# MinipHV3_2.net
KiCad netlist of a schematic drawn in EAGLE
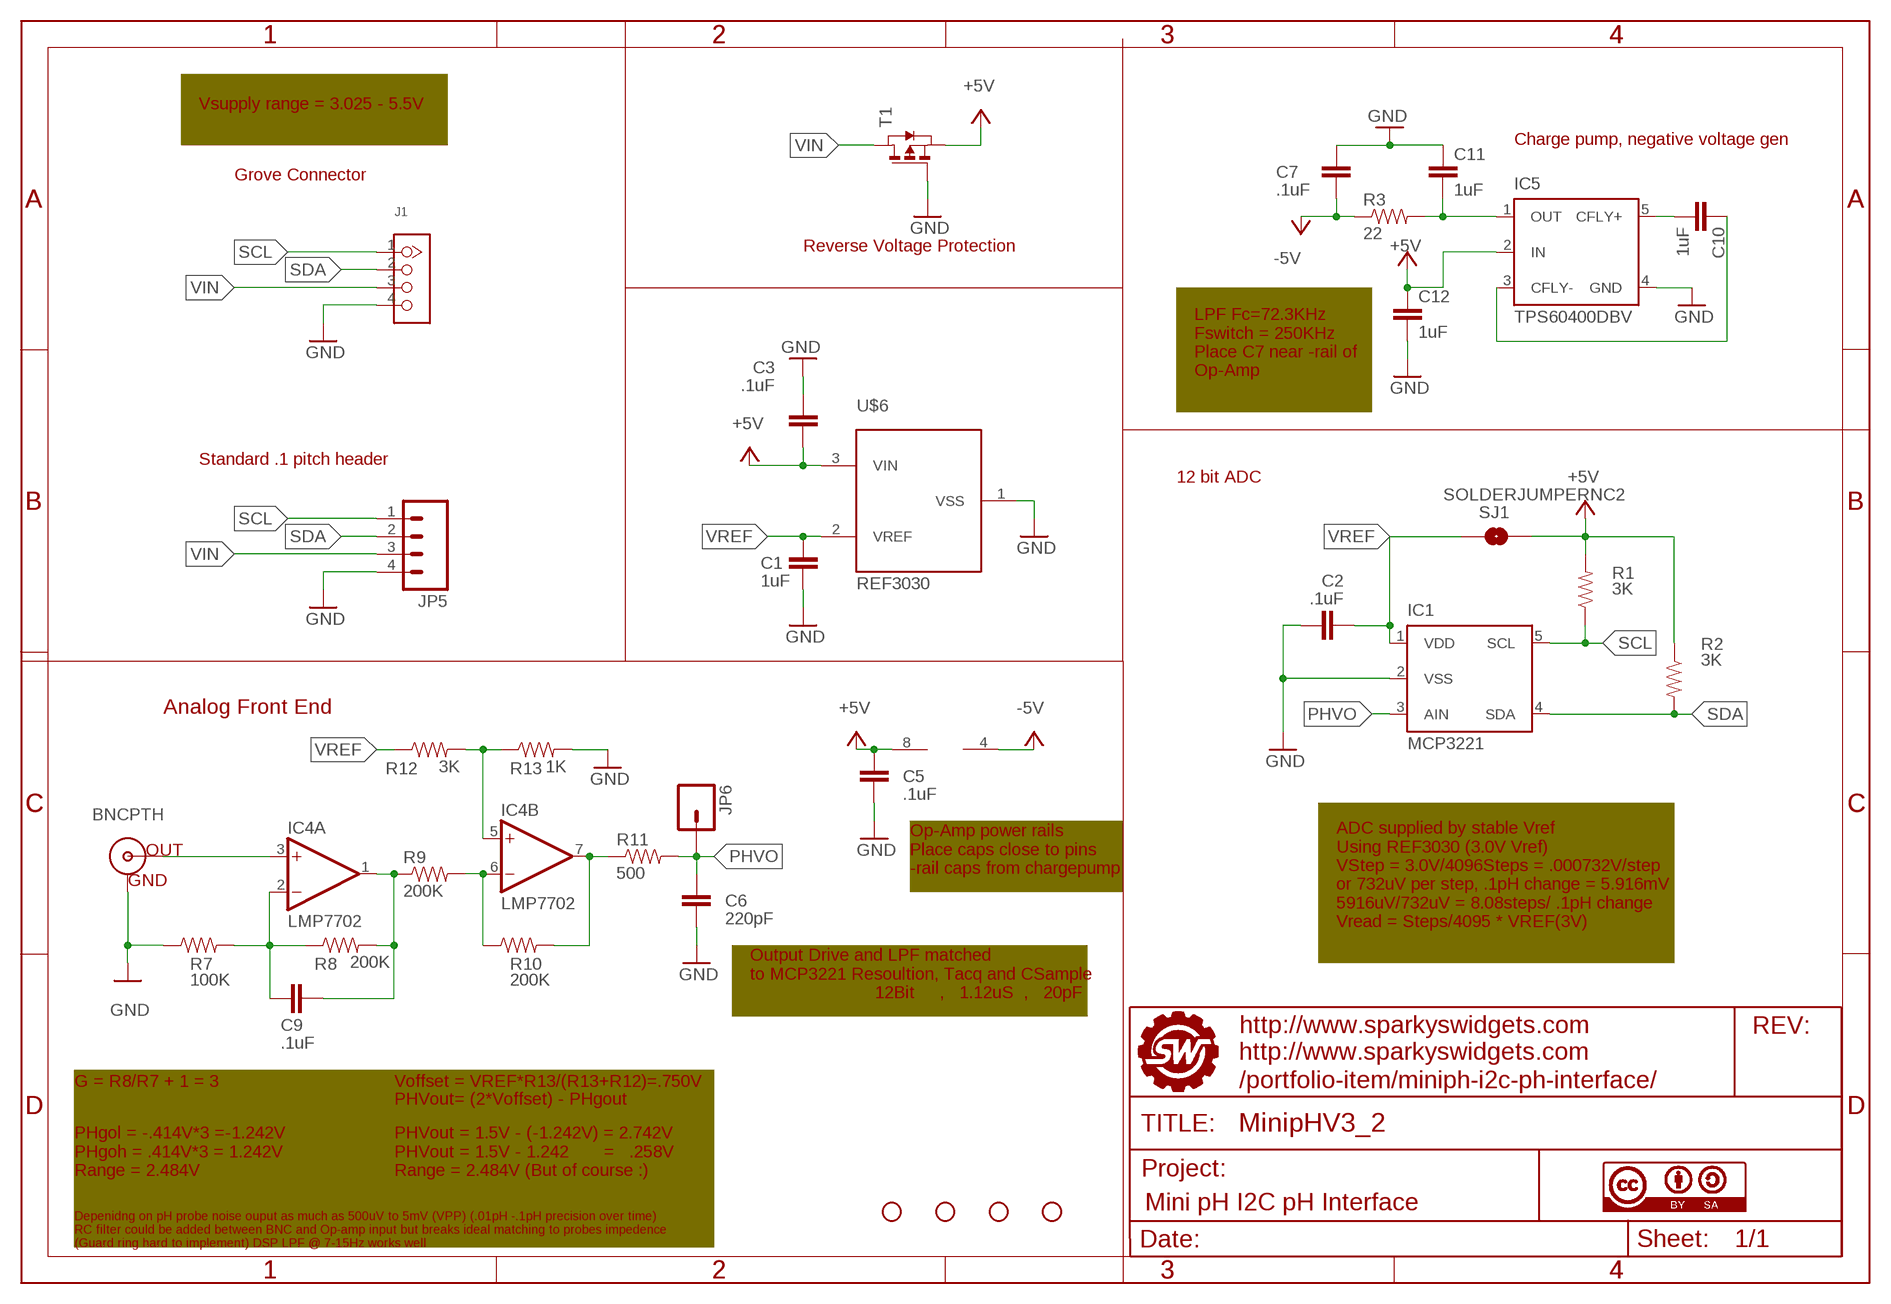
[diagram p0: schematic, sheet 1]

(export (version "E")
  (design (tool "Eeschema 10.0.6"))
  (components
    (comp (ref "C1")
      (value "1uF")
      (footprint "eagle-import:0805")
      (libsource (lib "eagle-import") (part "CAP0805"))
    )
    (comp (ref "C2")
      (value ".1uF")
      (footprint "eagle-import:0805")
      (libsource (lib "eagle-import") (part "CAP0805"))
    )
    (comp (ref "C3")
      (value ".1uF")
      (footprint "eagle-import:0805")
      (libsource (lib "eagle-import") (part "CAP0805"))
    )
    (comp (ref "C5")
      (value ".1uF")
      (footprint "eagle-import:0805")
      (libsource (lib "eagle-import") (part "CAP0805"))
    )
    (comp (ref "C6")
      (value "220pF")
      (footprint "eagle-import:0805")
      (libsource (lib "eagle-import") (part "CAP0805"))
    )
    (comp (ref "C7")
      (value ".1uF")
      (footprint "eagle-import:0805")
      (libsource (lib "eagle-import") (part "CAP0805"))
    )
    (comp (ref "C9")
      (value ".1uF")
      (footprint "eagle-import:0805")
      (libsource (lib "eagle-import") (part "CAP0805"))
    )
    (comp (ref "C10")
      (value "1uF")
      (footprint "eagle-import:0805")
      (libsource (lib "eagle-import") (part "CAP0805"))
    )
    (comp (ref "C11")
      (value "1uF")
      (footprint "eagle-import:0805")
      (libsource (lib "eagle-import") (part "CAP0805"))
    )
    (comp (ref "C12")
      (value "1uF")
      (footprint "eagle-import:0805")
      (libsource (lib "eagle-import") (part "CAP0805"))
    )
    (comp (ref "IC1")
      (value "MCP3221")
      (footprint "eagle-import:SOT23-DBV")
      (libsource (lib "eagle-import") (part "MCP3221"))
    )
    (comp (ref "IC4")
      (value "LMP7702")
      (footprint "eagle-import:SO08")
      (libsource (lib "eagle-import") (part "LM358D"))
    )
    (comp (ref "IC5")
      (value "TPS60400DBV")
      (footprint "eagle-import:SOT23-DBV")
      (libsource (lib "eagle-import") (part "TPS60400DBV"))
    )
    (comp (ref "J1")
      (value "TWIG-4P-2.0-2.0")
      (footprint "eagle-import:4P-2.0")
      (libsource (lib "eagle-import") (part "TWIG-4P-2.0-2.0"))
    )
    (comp (ref "JP1")
      (value "STAND-OFF")
      (footprint "eagle-import:STAND-OFF")
      (libsource (lib "eagle-import") (part "STAND-OFF"))
    )
    (comp (ref "JP2")
      (value "STAND-OFF")
      (footprint "eagle-import:STAND-OFF")
      (libsource (lib "eagle-import") (part "STAND-OFF"))
    )
    (comp (ref "JP3")
      (value "STAND-OFF")
      (footprint "eagle-import:STAND-OFF")
      (libsource (lib "eagle-import") (part "STAND-OFF"))
    )
    (comp (ref "JP4")
      (value "STAND-OFF")
      (footprint "eagle-import:STAND-OFF")
      (libsource (lib "eagle-import") (part "STAND-OFF"))
    )
    (comp (ref "JP5")
      (value "M04PTH")
      (footprint "eagle-import:1X04")
      (libsource (lib "eagle-import") (part "M04PTH"))
    )
    (comp (ref "JP6")
      (value "M01PTH")
      (footprint "eagle-import:1X01")
      (libsource (lib "eagle-import") (part "M01PTH"))
    )
    (comp (ref "R1")
      (value "3K")
      (footprint "eagle-import:0805")
      (libsource (lib "eagle-import") (part "RESISTOR0805-RES"))
    )
    (comp (ref "R2")
      (value "3K")
      (footprint "eagle-import:0805")
      (libsource (lib "eagle-import") (part "RESISTOR0805-RES"))
    )
    (comp (ref "R3")
      (value "22")
      (footprint "eagle-import:0805")
      (libsource (lib "eagle-import") (part "RESISTOR0805-RES"))
    )
    (comp (ref "R7")
      (value "100K")
      (footprint "eagle-import:0805")
      (libsource (lib "eagle-import") (part "RESISTOR0805-RES"))
    )
    (comp (ref "R8")
      (value "200K")
      (footprint "eagle-import:0805")
      (libsource (lib "eagle-import") (part "RESISTOR0805-RES"))
    )
    (comp (ref "R9")
      (value "200K")
      (footprint "eagle-import:0805")
      (libsource (lib "eagle-import") (part "RESISTOR0805-RES"))
    )
    (comp (ref "R10")
      (value "200K")
      (footprint "eagle-import:0805")
      (libsource (lib "eagle-import") (part "RESISTOR0805-RES"))
    )
    (comp (ref "R11")
      (value "500")
      (footprint "eagle-import:0805")
      (libsource (lib "eagle-import") (part "RESISTOR0805-RES"))
    )
    (comp (ref "R12")
      (value "3K")
      (footprint "eagle-import:0805")
      (libsource (lib "eagle-import") (part "RESISTOR0805-RES"))
    )
    (comp (ref "R13")
      (value "1K")
      (footprint "eagle-import:0805")
      (libsource (lib "eagle-import") (part "RESISTOR0805-RES"))
    )
    (comp (ref "SJ1")
      (value "SOLDERJUMPERNC2")
      (footprint "eagle-import:SJ_2S-NOTRACE")
      (libsource (lib "eagle-import") (part "SOLDERJUMPERNC2"))
    )
    (comp (ref "T1")
      (value "PMOSSOT23")
      (footprint "eagle-import:SOT-23")
      (libsource (lib "eagle-import") (part "PMOSSOT23"))
    )
    (comp (ref "U$2")
      (value "BNCPTH")
      (footprint "eagle-import:BNC")
      (libsource (lib "eagle-import") (part "BNCPTH"))
    )
    (comp (ref "U$4")
      (value "FRAME_MINIPH")
      (footprint "eagle-import:SWPCBLOGOWITHINFO")
      (fields
        (field (name "PROJECT") "Mini pH I2C pH Interface")
        (field (name "URL1") "/portfolio-item/miniph-i2c-ph-interface/")
      )
      (libsource (lib "eagle-import") (part "FRAME_MINIPH"))
    )
    (comp (ref "U$5")
      (value "CC-BY-SA")
      (footprint "eagle-import:CC-BY-SA")
      (libsource (lib "eagle-import") (part "CC-BY-SA"))
    )
    (comp (ref "U$6")
      (value "REF3030")
      (footprint "eagle-import:SOT-23")
      (libsource (lib "eagle-import") (part "MCP1541"))
    )
  )
  (nets
    (net (code "1") (name "+5V") (class "Default")
      (node (ref "C12") (pin "1") (pinfunction "1_1") (pintype "passive"))
      (node (ref "C3") (pin "1") (pinfunction "1_1") (pintype "passive"))
      (node (ref "C5") (pin "1") (pinfunction "1_1") (pintype "passive"))
      (node (ref "IC4") (pin "8") (pinfunction "V+_8") (pintype "power_in"))
      (node (ref "IC5") (pin "2") (pinfunction "IN_2") (pintype "input"))
      (node (ref "R1") (pin "2") (pinfunction "2_2") (pintype "passive"))
      (node (ref "R2") (pin "1") (pinfunction "1_1") (pintype "passive"))
      (node (ref "SJ1") (pin "2") (pinfunction "2_2") (pintype "passive"))
      (node (ref "T1") (pin "2") (pinfunction "S_2") (pintype "passive"))
      (node (ref "U$6") (pin "3") (pinfunction "VIN_3") (pintype "power_in"))
    )
    (net (code "2") (name "-5V") (class "Default")
      (node (ref "C7") (pin "2") (pinfunction "2_2") (pintype "passive"))
      (node (ref "IC4") (pin "4") (pinfunction "V-_4") (pintype "power_in"))
      (node (ref "R3") (pin "1") (pinfunction "1_1") (pintype "passive"))
    )
    (net (code "3") (name "GND") (class "Default")
      (node (ref "C1") (pin "2") (pinfunction "2_2") (pintype "passive"))
      (node (ref "C11") (pin "1") (pinfunction "1_1") (pintype "passive"))
      (node (ref "C12") (pin "2") (pinfunction "2_2") (pintype "passive"))
      (node (ref "C2") (pin "1") (pinfunction "1_1") (pintype "passive"))
      (node (ref "C3") (pin "2") (pinfunction "2_2") (pintype "passive"))
      (node (ref "C5") (pin "2") (pinfunction "2_2") (pintype "passive"))
      (node (ref "C6") (pin "2") (pinfunction "2_2") (pintype "passive"))
      (node (ref "C7") (pin "1") (pinfunction "1_1") (pintype "passive"))
      (node (ref "IC1") (pin "2") (pinfunction "VSS_2") (pintype "power_in"))
      (node (ref "IC5") (pin "4") (pinfunction "GND_4") (pintype "passive"))
      (node (ref "J1") (pin "4") (pinfunction "4_4") (pintype "bidirectional"))
      (node (ref "JP5") (pin "4") (pinfunction "4_4") (pintype "passive"))
      (node (ref "R13") (pin "2") (pinfunction "2_2") (pintype "passive"))
      (node (ref "R7") (pin "1") (pinfunction "1_1") (pintype "passive"))
      (node (ref "T1") (pin "3") (pinfunction "G_3") (pintype "passive"))
      (node (ref "U$2") (pin "GND") (pinfunction "GND_GND") (pintype "bidirectional"))
      (node (ref "U$6") (pin "1") (pinfunction "VSS_1") (pintype "power_in"))
    )
    (net (code "4") (name "Net-(IC4A-+IN)") (class "Default")
      (node (ref "IC4") (pin "3") (pinfunction "+IN_3") (pintype "input"))
      (node (ref "U$2") (pin "S") (pinfunction "OUT_S") (pintype "bidirectional"))
    )
    (net (code "5") (name "Net-(IC4A--IN)") (class "Default")
      (node (ref "C9") (pin "2") (pinfunction "2_2") (pintype "passive"))
      (node (ref "IC4") (pin "2") (pinfunction "-IN_2") (pintype "input"))
      (node (ref "R7") (pin "2") (pinfunction "2_2") (pintype "passive"))
      (node (ref "R8") (pin "1") (pinfunction "1_1") (pintype "passive"))
    )
    (net (code "6") (name "Net-(IC4A-OUT)") (class "Default")
      (node (ref "C9") (pin "1") (pinfunction "1_1") (pintype "passive"))
      (node (ref "IC4") (pin "1") (pinfunction "OUT_1") (pintype "output"))
      (node (ref "R8") (pin "2") (pinfunction "2_2") (pintype "passive"))
      (node (ref "R9") (pin "1") (pinfunction "1_1") (pintype "passive"))
    )
    (net (code "7") (name "Net-(IC4B-+IN)") (class "Default")
      (node (ref "IC4") (pin "5") (pinfunction "+IN_5") (pintype "input"))
      (node (ref "R12") (pin "2") (pinfunction "2_2") (pintype "passive"))
      (node (ref "R13") (pin "1") (pinfunction "1_1") (pintype "passive"))
    )
    (net (code "8") (name "Net-(IC4B--IN)") (class "Default")
      (node (ref "IC4") (pin "6") (pinfunction "-IN_6") (pintype "input"))
      (node (ref "R10") (pin "1") (pinfunction "1_1") (pintype "passive"))
      (node (ref "R9") (pin "2") (pinfunction "2_2") (pintype "passive"))
    )
    (net (code "9") (name "Net-(IC4B-OUT)") (class "Default")
      (node (ref "IC4") (pin "7") (pinfunction "OUT_7") (pintype "output"))
      (node (ref "R10") (pin "2") (pinfunction "2_2") (pintype "passive"))
      (node (ref "R11") (pin "1") (pinfunction "1_1") (pintype "passive"))
    )
    (net (code "10") (name "Net-(IC5-CFLY+)") (class "Default")
      (node (ref "C10") (pin "2") (pinfunction "2_2") (pintype "passive"))
      (node (ref "IC5") (pin "5") (pinfunction "CFLY+_5") (pintype "passive"))
    )
    (net (code "11") (name "Net-(IC5-CFLY-)") (class "Default")
      (node (ref "C10") (pin "1") (pinfunction "1_1") (pintype "passive"))
      (node (ref "IC5") (pin "3") (pinfunction "CFLY-_3") (pintype "power_in"))
    )
    (net (code "12") (name "Net-(IC5-OUT)") (class "Default")
      (node (ref "C11") (pin "2") (pinfunction "2_2") (pintype "passive"))
      (node (ref "IC5") (pin "1") (pinfunction "OUT_1") (pintype "input"))
      (node (ref "R3") (pin "2") (pinfunction "2_2") (pintype "passive"))
    )
    (net (code "13") (name "PHVO") (class "Default")
      (node (ref "C6") (pin "1") (pinfunction "1_1") (pintype "passive"))
      (node (ref "IC1") (pin "3") (pinfunction "AIN_3") (pintype "input"))
      (node (ref "JP6") (pin "1") (pinfunction "1_1") (pintype "passive"))
      (node (ref "R11") (pin "2") (pinfunction "2_2") (pintype "passive"))
    )
    (net (code "14") (name "SCL") (class "Default")
      (node (ref "IC1") (pin "5") (pinfunction "SCL_5") (pintype "bidirectional"))
      (node (ref "J1") (pin "1") (pinfunction "1_1") (pintype "bidirectional"))
      (node (ref "JP5") (pin "1") (pinfunction "1_1") (pintype "passive"))
      (node (ref "R1") (pin "1") (pinfunction "1_1") (pintype "passive"))
    )
    (net (code "15") (name "SDA") (class "Default")
      (node (ref "IC1") (pin "4") (pinfunction "SDA_4") (pintype "bidirectional"))
      (node (ref "J1") (pin "2") (pinfunction "2_2") (pintype "bidirectional"))
      (node (ref "JP5") (pin "2") (pinfunction "2_2") (pintype "passive"))
      (node (ref "R2") (pin "2") (pinfunction "2_2") (pintype "passive"))
    )
    (net (code "16") (name "VIN") (class "Default")
      (node (ref "J1") (pin "3") (pinfunction "3_3") (pintype "bidirectional"))
      (node (ref "JP5") (pin "3") (pinfunction "3_3") (pintype "passive"))
      (node (ref "T1") (pin "1") (pinfunction "D_1") (pintype "passive"))
    )
    (net (code "17") (name "VREF") (class "Default")
      (node (ref "C1") (pin "1") (pinfunction "1_1") (pintype "passive"))
      (node (ref "C2") (pin "2") (pinfunction "2_2") (pintype "passive"))
      (node (ref "IC1") (pin "1") (pinfunction "VDD_1") (pintype "power_in"))
      (node (ref "R12") (pin "1") (pinfunction "1_1") (pintype "passive"))
      (node (ref "SJ1") (pin "1") (pinfunction "1_1") (pintype "passive"))
      (node (ref "U$6") (pin "2") (pinfunction "VREF_2") (pintype "output"))
    )
  )
)
